# internal_excitation_w_gp.net
KiCad netlist of a schematic drawn in EAGLE
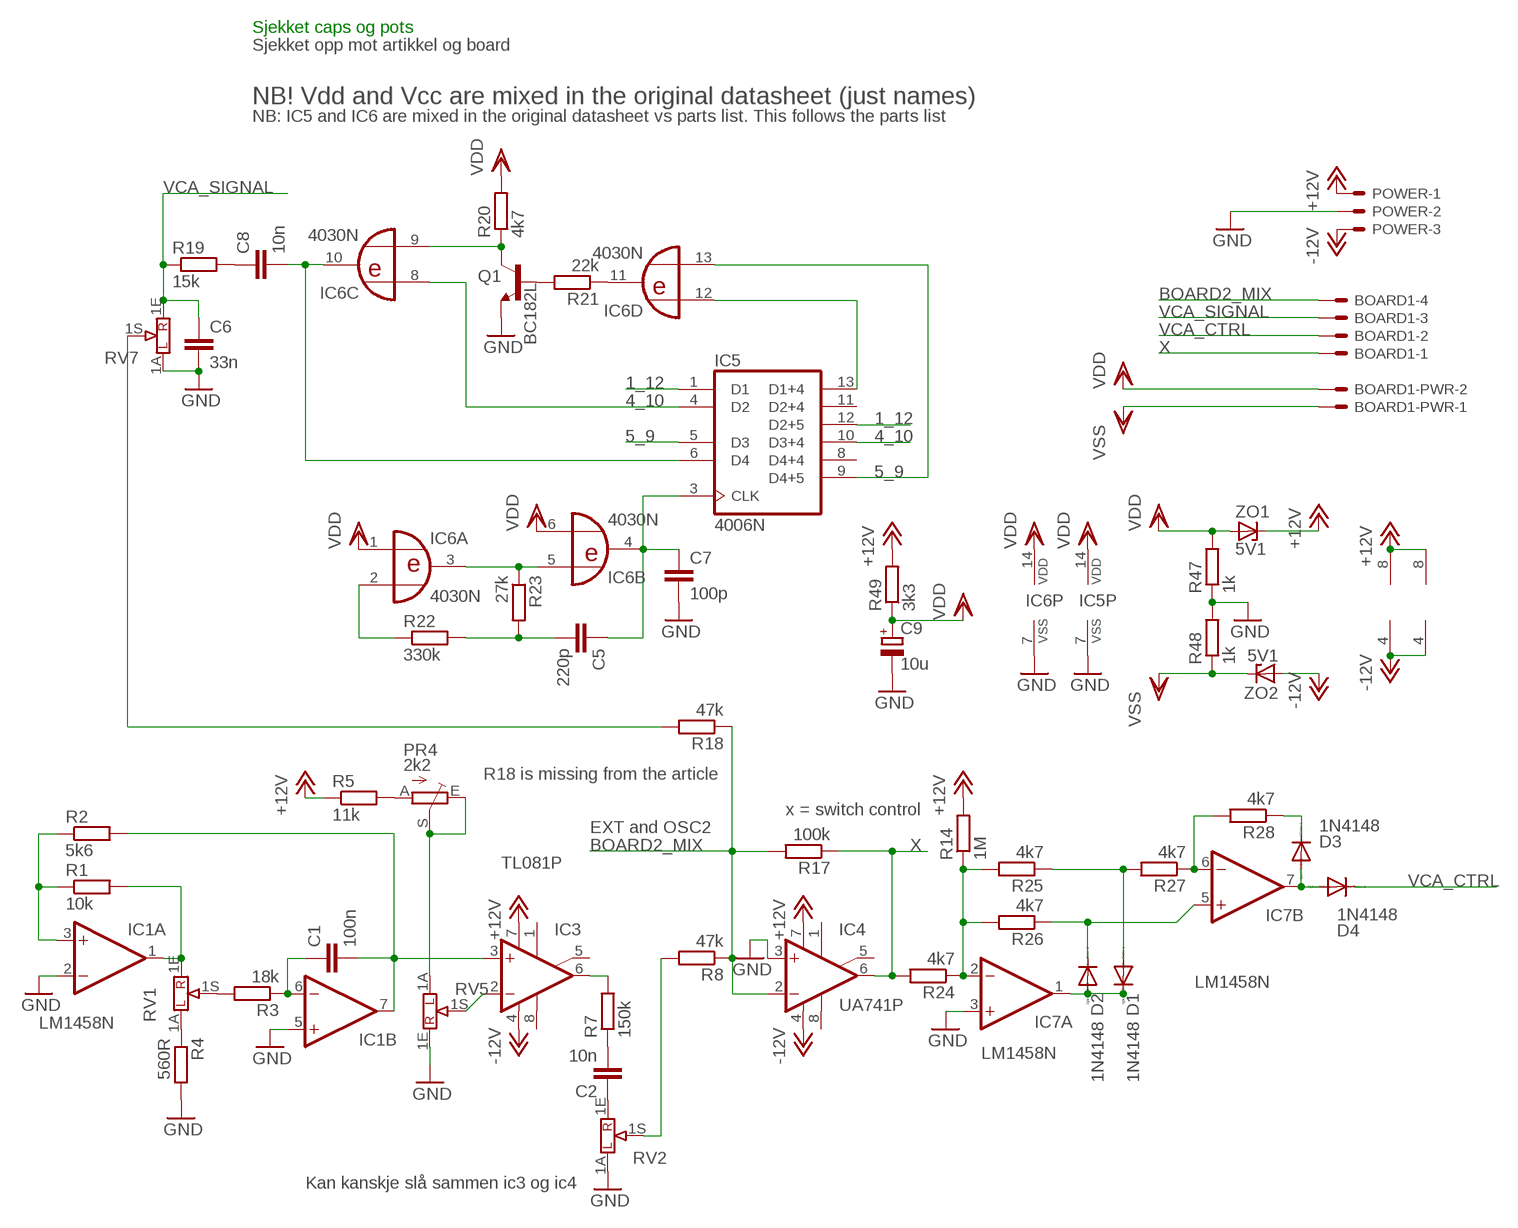
[diagram p0: schematic, sheet 1]

(export (version "E")
  (design (tool "Eeschema 10.0.6"))
  (components
    (comp (ref "BOARD1")
      (value "22-23-2041")
      (footprint "eagle-import:22-23-2041")
      (fields (field (name "MF") "MOLEX"))
      (libsource (lib "eagle-import") (part "22-23-2041"))
    )
    (comp (ref "BOARD1-PWR")
      (value "22-23-2021")
      (footprint "eagle-import:22-23-2021")
      (fields (field (name "MF") "MOLEX"))
      (libsource (lib "eagle-import") (part "22-23-2021"))
    )
    (comp (ref "C1")
      (value "100n")
      (footprint "eagle-import:C050-030X075")
      (libsource (lib "eagle-import") (part "C-EU050-030X075"))
    )
    (comp (ref "C2")
      (value "10n")
      (footprint "eagle-import:C025-025X050")
      (libsource (lib "eagle-import") (part "C-EU025-025X050"))
    )
    (comp (ref "C5")
      (value "220p")
      (footprint "eagle-import:C025-025X050")
      (libsource (lib "eagle-import") (part "C-EU025-025X050"))
    )
    (comp (ref "C6")
      (value "33n")
      (footprint "eagle-import:C050-030X075")
      (libsource (lib "eagle-import") (part "C-EU050-030X075"))
    )
    (comp (ref "C7")
      (value "100p")
      (footprint "eagle-import:C025-025X050")
      (libsource (lib "eagle-import") (part "C-EU025-025X050"))
    )
    (comp (ref "C8")
      (value "10n")
      (footprint "eagle-import:C050-030X075")
      (libsource (lib "eagle-import") (part "C-EU050-030X075"))
    )
    (comp (ref "C9")
      (value "10u")
      (footprint "eagle-import:E2,5-5")
      (libsource (lib "eagle-import") (part "CPOL-EUE2.5-5"))
    )
    (comp (ref "D1")
      (value "1N4148")
      (footprint "eagle-import:DO35-5J")
      (libsource (lib "eagle-import") (part "1N4148DOJ35-5"))
    )
    (comp (ref "D2")
      (value "1N4148")
      (footprint "eagle-import:DO35-5J")
      (libsource (lib "eagle-import") (part "1N4148DOJ35-5"))
    )
    (comp (ref "D3")
      (value "1N4148")
      (footprint "eagle-import:DO35-5J")
      (libsource (lib "eagle-import") (part "1N4148DOJ35-5"))
    )
    (comp (ref "D4")
      (value "1N4148")
      (footprint "eagle-import:DO35-5J")
      (libsource (lib "eagle-import") (part "1N4148DOJ35-5"))
    )
    (comp (ref "IC1")
      (value "LM1458N")
      (footprint "eagle-import:DIL08")
      (libsource (lib "eagle-import") (part "1458NLM"))
    )
    (comp (ref "IC3")
      (value "TL081P")
      (footprint "eagle-import:DIL08")
      (libsource (lib "eagle-import") (part "TL081P"))
    )
    (comp (ref "IC4")
      (value "UA741P")
      (footprint "eagle-import:DIL08")
      (libsource (lib "eagle-import") (part "741PUA"))
    )
    (comp (ref "IC5")
      (value "4006N")
      (footprint "eagle-import:DIL14")
      (libsource (lib "eagle-import") (part "4006N"))
    )
    (comp (ref "IC6")
      (value "4030N")
      (footprint "eagle-import:DIL14")
      (libsource (lib "eagle-import") (part "4030N"))
    )
    (comp (ref "IC7")
      (value "LM1458N")
      (footprint "eagle-import:DIL08")
      (libsource (lib "eagle-import") (part "1458NLM"))
    )
    (comp (ref "POWER")
      (value "KK-156-3")
      (footprint "eagle-import:KK-156-3")
      (libsource (lib "eagle-import") (part "KK-156-3"))
    )
    (comp (ref "PR4")
      (value "2k2")
      (footprint "eagle-import:CA9V")
      (libsource (lib "eagle-import") (part "TRIM_EU-CA9V"))
    )
    (comp (ref "Q1")
      (value "BC182L")
      (footprint "eagle-import:TO92-ECB")
      (libsource (lib "eagle-import") (part "-NPN-TO92-ECB"))
    )
    (comp (ref "R1")
      (value "10k")
      (footprint "eagle-import:0207_7")
      (libsource (lib "eagle-import") (part "R-EU_0207/7"))
    )
    (comp (ref "R2")
      (value "5k6")
      (footprint "eagle-import:0207_7")
      (libsource (lib "eagle-import") (part "R-EU_0207/7"))
    )
    (comp (ref "R3")
      (value "18k")
      (footprint "eagle-import:0207_7")
      (libsource (lib "eagle-import") (part "R-EU_0207/7"))
    )
    (comp (ref "R4")
      (value "560R")
      (footprint "eagle-import:0207_7")
      (libsource (lib "eagle-import") (part "R-EU_0207/7"))
    )
    (comp (ref "R5")
      (value "11k")
      (footprint "eagle-import:0207_7")
      (libsource (lib "eagle-import") (part "R-EU_0207/7"))
    )
    (comp (ref "R7")
      (value "150k")
      (footprint "eagle-import:0207_7")
      (libsource (lib "eagle-import") (part "R-EU_0207/7"))
    )
    (comp (ref "R8")
      (value "47k")
      (footprint "eagle-import:0207_7")
      (libsource (lib "eagle-import") (part "R-EU_0207/7"))
    )
    (comp (ref "R14")
      (value "1M")
      (footprint "eagle-import:0207_7")
      (libsource (lib "eagle-import") (part "R-EU_0207/7"))
    )
    (comp (ref "R17")
      (value "100k")
      (footprint "eagle-import:0207_7")
      (libsource (lib "eagle-import") (part "R-EU_0207/7"))
    )
    (comp (ref "R18")
      (value "47k")
      (footprint "eagle-import:0207_7")
      (libsource (lib "eagle-import") (part "R-EU_0207/7"))
    )
    (comp (ref "R19")
      (value "15k")
      (footprint "eagle-import:0207_7")
      (libsource (lib "eagle-import") (part "R-EU_0207/7"))
    )
    (comp (ref "R20")
      (value "4k7")
      (footprint "eagle-import:0207_7")
      (libsource (lib "eagle-import") (part "R-EU_0207/7"))
    )
    (comp (ref "R21")
      (value "22k")
      (footprint "eagle-import:0207_7")
      (libsource (lib "eagle-import") (part "R-EU_0207/7"))
    )
    (comp (ref "R22")
      (value "330k")
      (footprint "eagle-import:0207_7")
      (libsource (lib "eagle-import") (part "R-EU_0207/7"))
    )
    (comp (ref "R23")
      (value "27k")
      (footprint "eagle-import:0207_7")
      (libsource (lib "eagle-import") (part "R-EU_0207/7"))
    )
    (comp (ref "R24")
      (value "4k7")
      (footprint "eagle-import:0207_7")
      (libsource (lib "eagle-import") (part "R-EU_0207/7"))
    )
    (comp (ref "R25")
      (value "4k7")
      (footprint "eagle-import:0207_7")
      (libsource (lib "eagle-import") (part "R-EU_0207/7"))
    )
    (comp (ref "R26")
      (value "4k7")
      (footprint "eagle-import:0207_7")
      (libsource (lib "eagle-import") (part "R-EU_0207/7"))
    )
    (comp (ref "R27")
      (value "4k7")
      (footprint "eagle-import:0207_7")
      (libsource (lib "eagle-import") (part "R-EU_0207/7"))
    )
    (comp (ref "R28")
      (value "4k7")
      (footprint "eagle-import:0207_7")
      (libsource (lib "eagle-import") (part "R-EU_0207/7"))
    )
    (comp (ref "R47")
      (value "1k")
      (footprint "eagle-import:0207_7")
      (libsource (lib "eagle-import") (part "R-EU_0207/7"))
    )
    (comp (ref "R48")
      (value "1k")
      (footprint "eagle-import:0207_7")
      (libsource (lib "eagle-import") (part "R-EU_0207/7"))
    )
    (comp (ref "R49")
      (value "3k3")
      (footprint "eagle-import:0207_7")
      (libsource (lib "eagle-import") (part "R-EU_0207/7"))
    )
    (comp (ref "RV1")
      (value "10k log")
      (footprint "eagle-import:POT16_W_BRACKET")
      (libsource (lib "eagle-import") (part "POT16_W_BRACKET{dblquote}{dblquote}"))
    )
    (comp (ref "RV2")
      (value "10k log")
      (footprint "eagle-import:POT16_W_BRACKET")
      (libsource (lib "eagle-import") (part "POT16_W_BRACKET{dblquote}{dblquote}"))
    )
    (comp (ref "RV5")
      (value "10k")
      (footprint "eagle-import:POT16_W_BRACKET")
      (libsource (lib "eagle-import") (part "POT16_W_BRACKET{dblquote}{dblquote}"))
    )
    (comp (ref "RV7")
      (value "10k")
      (footprint "eagle-import:POT16_W_BRACKET")
      (libsource (lib "eagle-import") (part "POT16_W_BRACKET{dblquote}{dblquote}"))
    )
    (comp (ref "ZO1")
      (value "5V1")
      (footprint "eagle-import:ZDIO-5")
      (libsource (lib "eagle-import") (part "ZENER-DIODEZD-5"))
    )
    (comp (ref "ZO2")
      (value "5V1")
      (footprint "eagle-import:ZDIO-5")
      (libsource (lib "eagle-import") (part "ZENER-DIODEZD-5"))
    )
  )
  (nets
    (net (code "1") (name "+12V") (class "Default")
      (node (ref "IC1") (pin "8") (pinfunction "V+_8") (pintype "power_in"))
      (node (ref "IC3") (pin "7") (pinfunction "V+_7") (pintype "power_in"))
      (node (ref "IC4") (pin "7") (pinfunction "V+_7") (pintype "power_in"))
      (node (ref "IC7") (pin "8") (pinfunction "V+_8") (pintype "power_in"))
      (node (ref "POWER") (pin "1") (pinfunction "S_1") (pintype "passive"))
      (node (ref "R14") (pin "2") (pinfunction "2_2") (pintype "passive"))
      (node (ref "R49") (pin "2") (pinfunction "2_2") (pintype "passive"))
      (node (ref "R5") (pin "1") (pinfunction "1_1") (pintype "passive"))
      (node (ref "ZO1") (pin "C") (pinfunction "C_C") (pintype "passive"))
    )
    (net (code "2") (name "-12V") (class "Default")
      (node (ref "IC1") (pin "4") (pinfunction "V-_4") (pintype "power_in"))
      (node (ref "IC3") (pin "4") (pinfunction "V-_4") (pintype "power_in"))
      (node (ref "IC4") (pin "4") (pinfunction "V-_4") (pintype "power_in"))
      (node (ref "IC7") (pin "4") (pinfunction "V-_4") (pintype "power_in"))
      (node (ref "POWER") (pin "3") (pinfunction "S_3") (pintype "passive"))
      (node (ref "ZO2") (pin "A") (pinfunction "A_A") (pintype "passive"))
    )
    (net (code "3") (name "/1_12") (class "Default")
      (node (ref "IC5") (pin "1") (pinfunction "D1_1") (pintype "input"))
      (node (ref "IC5") (pin "12") (pinfunction "D2+5_12") (pintype "output"))
    )
    (net (code "4") (name "/4_10") (class "Default")
      (node (ref "IC5") (pin "10") (pinfunction "D3+4_10") (pintype "output"))
      (node (ref "IC5") (pin "4") (pinfunction "D2_4") (pintype "input"))
      (node (ref "IC6") (pin "8") (pinfunction "I0_8") (pintype "input"))
    )
    (net (code "5") (name "/5_9") (class "Default")
      (node (ref "IC5") (pin "5") (pinfunction "D3_5") (pintype "input"))
      (node (ref "IC5") (pin "9") (pinfunction "D4+5_9") (pintype "output"))
      (node (ref "IC6") (pin "13") (pinfunction "I1_13") (pintype "input"))
    )
    (net (code "6") (name "/BOARD2_MIX") (class "Default")
      (node (ref "BOARD1") (pin "4") (pinfunction "S_4") (pintype "passive"))
      (node (ref "IC4") (pin "2") (pinfunction "-IN_2") (pintype "input"))
      (node (ref "R17") (pin "2") (pinfunction "2_2") (pintype "passive"))
      (node (ref "R18") (pin "1") (pinfunction "1_1") (pintype "passive"))
      (node (ref "R8") (pin "1") (pinfunction "1_1") (pintype "passive"))
    )
    (net (code "7") (name "/VCA_CTRL") (class "Default")
      (node (ref "BOARD1") (pin "2") (pinfunction "S_2") (pintype "passive"))
      (node (ref "D4") (pin "C") (pinfunction "C_C") (pintype "passive"))
    )
    (net (code "8") (name "/VCA_SIGNAL") (class "Default")
      (node (ref "BOARD1") (pin "3") (pinfunction "S_3") (pintype "passive"))
      (node (ref "C6") (pin "1") (pinfunction "1_1") (pintype "passive"))
      (node (ref "R19") (pin "1") (pinfunction "1_1") (pintype "passive"))
      (node (ref "RV7") (pin "1E") (pinfunction "1E_1E") (pintype "passive"))
    )
    (net (code "9") (name "/X") (class "Default")
      (node (ref "BOARD1") (pin "1") (pinfunction "S_1") (pintype "passive"))
      (node (ref "IC4") (pin "6") (pinfunction "OUT_6") (pintype "output"))
      (node (ref "R17") (pin "1") (pinfunction "1_1") (pintype "passive"))
      (node (ref "R24") (pin "2") (pinfunction "2_2") (pintype "passive"))
    )
    (net (code "10") (name "GND") (class "Default")
      (node (ref "C6") (pin "2") (pinfunction "2_2") (pintype "passive"))
      (node (ref "C7") (pin "2") (pinfunction "2_2") (pintype "passive"))
      (node (ref "C9") (pin "-") (pinfunction "-_-") (pintype "passive"))
      (node (ref "IC1") (pin "2") (pinfunction "-IN_2") (pintype "input"))
      (node (ref "IC1") (pin "5") (pinfunction "+IN_5") (pintype "input"))
      (node (ref "IC4") (pin "3") (pinfunction "+IN_3") (pintype "input"))
      (node (ref "IC5") (pin "7") (pinfunction "VSS_7") (pintype "power_in"))
      (node (ref "IC6") (pin "7") (pinfunction "VSS_7") (pintype "power_in"))
      (node (ref "IC7") (pin "3") (pinfunction "+IN_3") (pintype "input"))
      (node (ref "POWER") (pin "2") (pinfunction "S_2") (pintype "passive"))
      (node (ref "Q1") (pin "E") (pinfunction "E_E") (pintype "passive"))
      (node (ref "R4") (pin "2") (pinfunction "2_2") (pintype "passive"))
      (node (ref "R47") (pin "1") (pinfunction "1_1") (pintype "passive"))
      (node (ref "R48") (pin "2") (pinfunction "2_2") (pintype "passive"))
      (node (ref "RV2") (pin "1A") (pinfunction "1A_1A") (pintype "passive"))
      (node (ref "RV5") (pin "1E") (pinfunction "1E_1E") (pintype "passive"))
      (node (ref "RV7") (pin "1A") (pinfunction "1A_1A") (pintype "passive"))
    )
    (net (code "11") (name "Net-(C2-Pad1)") (class "Default")
      (node (ref "C2") (pin "1") (pinfunction "1_1") (pintype "passive"))
      (node (ref "RV2") (pin "1E") (pinfunction "1E_1E") (pintype "passive"))
    )
    (net (code "12") (name "Net-(C2-Pad2)") (class "Default")
      (node (ref "C2") (pin "2") (pinfunction "2_2") (pintype "passive"))
      (node (ref "R7") (pin "1") (pinfunction "1_1") (pintype "passive"))
    )
    (net (code "13") (name "Net-(C5-Pad2)") (class "Default")
      (node (ref "C5") (pin "2") (pinfunction "2_2") (pintype "passive"))
      (node (ref "R22") (pin "2") (pinfunction "2_2") (pintype "passive"))
      (node (ref "R23") (pin "2") (pinfunction "2_2") (pintype "passive"))
    )
    (net (code "14") (name "Net-(C8-Pad1)") (class "Default")
      (node (ref "C8") (pin "1") (pinfunction "1_1") (pintype "passive"))
      (node (ref "R19") (pin "2") (pinfunction "2_2") (pintype "passive"))
    )
    (net (code "15") (name "Net-(D1-PadA)") (class "Default")
      (node (ref "D1") (pin "A") (pinfunction "A_A") (pintype "passive"))
      (node (ref "R25") (pin "1") (pinfunction "1_1") (pintype "passive"))
      (node (ref "R27") (pin "2") (pinfunction "2_2") (pintype "passive"))
    )
    (net (code "16") (name "Net-(D3-PadC)") (class "Default")
      (node (ref "D3") (pin "C") (pinfunction "C_C") (pintype "passive"))
      (node (ref "R28") (pin "1") (pinfunction "1_1") (pintype "passive"))
    )
    (net (code "17") (name "Net-(IC1A-+IN)") (class "Default")
      (node (ref "IC1") (pin "3") (pinfunction "+IN_3") (pintype "input"))
      (node (ref "R1") (pin "1") (pinfunction "1_1") (pintype "passive"))
      (node (ref "R2") (pin "1") (pinfunction "1_1") (pintype "passive"))
    )
    (net (code "18") (name "Net-(IC1A-OUT)") (class "Default")
      (node (ref "IC1") (pin "1") (pinfunction "OUT_1") (pintype "output"))
      (node (ref "R1") (pin "2") (pinfunction "2_2") (pintype "passive"))
      (node (ref "RV1") (pin "1E") (pinfunction "1E_1E") (pintype "passive"))
    )
    (net (code "19") (name "Net-(IC1B--IN)") (class "Default")
      (node (ref "C1") (pin "1") (pinfunction "1_1") (pintype "passive"))
      (node (ref "IC1") (pin "6") (pinfunction "-IN_6") (pintype "input"))
      (node (ref "R3") (pin "1") (pinfunction "1_1") (pintype "passive"))
    )
    (net (code "20") (name "Net-(IC1B-OUT)") (class "Default")
      (node (ref "C1") (pin "2") (pinfunction "2_2") (pintype "passive"))
      (node (ref "IC1") (pin "7") (pinfunction "OUT_7") (pintype "output"))
      (node (ref "IC3") (pin "3") (pinfunction "+IN_3") (pintype "input"))
      (node (ref "R2") (pin "2") (pinfunction "2_2") (pintype "passive"))
    )
    (net (code "21") (name "Net-(IC3--IN)") (class "Default")
      (node (ref "IC3") (pin "2") (pinfunction "-IN_2") (pintype "input"))
      (node (ref "RV5") (pin "1S") (pinfunction "1S_1S") (pintype "passive"))
    )
    (net (code "22") (name "Net-(IC3-OUT)") (class "Default")
      (node (ref "IC3") (pin "6") (pinfunction "OUT_6") (pintype "output"))
      (node (ref "R7") (pin "2") (pinfunction "2_2") (pintype "passive"))
    )
    (net (code "23") (name "Net-(IC5A-CLK)") (class "Default")
      (node (ref "C5") (pin "1") (pinfunction "1_1") (pintype "passive"))
      (node (ref "C7") (pin "1") (pinfunction "1_1") (pintype "passive"))
      (node (ref "IC5") (pin "3") (pinfunction "CLK_3") (pintype "input"))
      (node (ref "IC6") (pin "4") (pinfunction "O_4") (pintype "output"))
    )
    (net (code "24") (name "Net-(IC5A-D1+4)") (class "Default")
      (node (ref "IC5") (pin "13") (pinfunction "D1+4_13") (pintype "output"))
      (node (ref "IC6") (pin "12") (pinfunction "I0_12") (pintype "input"))
    )
    (net (code "25") (name "Net-(IC5A-D4)") (class "Default")
      (node (ref "C8") (pin "2") (pinfunction "2_2") (pintype "passive"))
      (node (ref "IC5") (pin "6") (pinfunction "D4_6") (pintype "input"))
      (node (ref "IC6") (pin "10") (pinfunction "O_10") (pintype "output"))
    )
    (net (code "26") (name "Net-(IC6A-I1)") (class "Default")
      (node (ref "IC6") (pin "2") (pinfunction "I1_2") (pintype "input"))
      (node (ref "R22") (pin "1") (pinfunction "1_1") (pintype "passive"))
    )
    (net (code "27") (name "Net-(IC6A-O)") (class "Default")
      (node (ref "IC6") (pin "3") (pinfunction "O_3") (pintype "output"))
      (node (ref "IC6") (pin "5") (pinfunction "I0_5") (pintype "input"))
      (node (ref "R23") (pin "1") (pinfunction "1_1") (pintype "passive"))
    )
    (net (code "28") (name "Net-(IC6C-I1)") (class "Default")
      (node (ref "IC6") (pin "9") (pinfunction "I1_9") (pintype "input"))
      (node (ref "Q1") (pin "C") (pinfunction "C_C") (pintype "passive"))
      (node (ref "R20") (pin "1") (pinfunction "1_1") (pintype "passive"))
    )
    (net (code "29") (name "Net-(IC6D-O)") (class "Default")
      (node (ref "IC6") (pin "11") (pinfunction "O_11") (pintype "output"))
      (node (ref "R21") (pin "1") (pinfunction "1_1") (pintype "passive"))
    )
    (net (code "30") (name "Net-(IC7A--IN)") (class "Default")
      (node (ref "IC7") (pin "2") (pinfunction "-IN_2") (pintype "input"))
      (node (ref "R14") (pin "1") (pinfunction "1_1") (pintype "passive"))
      (node (ref "R24") (pin "1") (pinfunction "1_1") (pintype "passive"))
      (node (ref "R25") (pin "2") (pinfunction "2_2") (pintype "passive"))
      (node (ref "R26") (pin "2") (pinfunction "2_2") (pintype "passive"))
    )
    (net (code "31") (name "Net-(IC7A-OUT)") (class "Default")
      (node (ref "D1") (pin "C") (pinfunction "C_C") (pintype "passive"))
      (node (ref "D2") (pin "A") (pinfunction "A_A") (pintype "passive"))
      (node (ref "IC7") (pin "1") (pinfunction "OUT_1") (pintype "output"))
    )
    (net (code "32") (name "Net-(IC7B-+IN)") (class "Default")
      (node (ref "D2") (pin "C") (pinfunction "C_C") (pintype "passive"))
      (node (ref "IC7") (pin "5") (pinfunction "+IN_5") (pintype "input"))
      (node (ref "R26") (pin "1") (pinfunction "1_1") (pintype "passive"))
    )
    (net (code "33") (name "Net-(IC7B--IN)") (class "Default")
      (node (ref "IC7") (pin "6") (pinfunction "-IN_6") (pintype "input"))
      (node (ref "R27") (pin "1") (pinfunction "1_1") (pintype "passive"))
      (node (ref "R28") (pin "2") (pinfunction "2_2") (pintype "passive"))
    )
    (net (code "34") (name "Net-(IC7B-OUT)") (class "Default")
      (node (ref "D3") (pin "A") (pinfunction "A_A") (pintype "passive"))
      (node (ref "D4") (pin "A") (pinfunction "A_A") (pintype "passive"))
      (node (ref "IC7") (pin "7") (pinfunction "OUT_7") (pintype "output"))
    )
    (net (code "35") (name "Net-(PR4-PadA)") (class "Default")
      (node (ref "PR4") (pin "A") (pinfunction "A_A") (pintype "passive"))
      (node (ref "R5") (pin "2") (pinfunction "2_2") (pintype "passive"))
    )
    (net (code "36") (name "Net-(PR4-PadE)") (class "Default")
      (node (ref "PR4") (pin "E") (pinfunction "E_E") (pintype "passive"))
      (node (ref "PR4") (pin "S") (pinfunction "S_S") (pintype "passive"))
      (node (ref "RV5") (pin "1A") (pinfunction "1A_1A") (pintype "passive"))
    )
    (net (code "37") (name "Net-(Q1-PadB)") (class "Default")
      (node (ref "Q1") (pin "B") (pinfunction "B_B") (pintype "passive"))
      (node (ref "R21") (pin "2") (pinfunction "2_2") (pintype "passive"))
    )
    (net (code "38") (name "Net-(R3-Pad2)") (class "Default")
      (node (ref "R3") (pin "2") (pinfunction "2_2") (pintype "passive"))
      (node (ref "RV1") (pin "1S") (pinfunction "1S_1S") (pintype "passive"))
    )
    (net (code "39") (name "Net-(R4-Pad1)") (class "Default")
      (node (ref "R4") (pin "1") (pinfunction "1_1") (pintype "passive"))
      (node (ref "RV1") (pin "1A") (pinfunction "1A_1A") (pintype "passive"))
    )
    (net (code "40") (name "Net-(R8-Pad2)") (class "Default")
      (node (ref "R8") (pin "2") (pinfunction "2_2") (pintype "passive"))
      (node (ref "RV2") (pin "1S") (pinfunction "1S_1S") (pintype "passive"))
    )
    (net (code "41") (name "Net-(R18-Pad2)") (class "Default")
      (node (ref "R18") (pin "2") (pinfunction "2_2") (pintype "passive"))
      (node (ref "RV7") (pin "1S") (pinfunction "1S_1S") (pintype "passive"))
    )
    (net (code "42") (name "VDD") (class "Default")
      (node (ref "BOARD1-PWR") (pin "2") (pinfunction "S_2") (pintype "passive"))
      (node (ref "C9") (pin "+") (pinfunction "+_+") (pintype "passive"))
      (node (ref "IC5") (pin "14") (pinfunction "VDD_14") (pintype "power_in"))
      (node (ref "IC6") (pin "1") (pinfunction "I0_1") (pintype "input"))
      (node (ref "IC6") (pin "14") (pinfunction "VDD_14") (pintype "power_in"))
      (node (ref "IC6") (pin "6") (pinfunction "I1_6") (pintype "input"))
      (node (ref "R20") (pin "2") (pinfunction "2_2") (pintype "passive"))
      (node (ref "R47") (pin "2") (pinfunction "2_2") (pintype "passive"))
      (node (ref "R49") (pin "1") (pinfunction "1_1") (pintype "passive"))
      (node (ref "ZO1") (pin "A") (pinfunction "A_A") (pintype "passive"))
    )
    (net (code "43") (name "VSS") (class "Default")
      (node (ref "BOARD1-PWR") (pin "1") (pinfunction "S_1") (pintype "passive"))
      (node (ref "R48") (pin "1") (pinfunction "1_1") (pintype "passive"))
      (node (ref "ZO2") (pin "C") (pinfunction "C_C") (pintype "passive"))
    )
    (net (code "44") (name "unconnected-(IC3-ON1-Pad1)") (class "Default")
      (node (ref "IC3") (pin "1") (pinfunction "ON1_1") (pintype "passive"))
    )
    (net (code "45") (name "unconnected-(IC3-ON2-Pad5)") (class "Default")
      (node (ref "IC3") (pin "5") (pinfunction "ON2_5") (pintype "passive"))
    )
    (net (code "46") (name "unconnected-(IC3-OPT-Pad8)") (class "Default")
      (node (ref "IC3") (pin "8") (pinfunction "OPT_8") (pintype "passive"))
    )
    (net (code "47") (name "unconnected-(IC4-ON1-Pad1)") (class "Default")
      (node (ref "IC4") (pin "1") (pinfunction "ON1_1") (pintype "passive"))
    )
    (net (code "48") (name "unconnected-(IC4-ON2-Pad5)") (class "Default")
      (node (ref "IC4") (pin "5") (pinfunction "ON2_5") (pintype "passive"))
    )
    (net (code "49") (name "unconnected-(IC4-OPT-Pad8)") (class "Default")
      (node (ref "IC4") (pin "8") (pinfunction "OPT_8") (pintype "passive"))
    )
    (net (code "50") (name "unconnected-(IC5A-D2+4-Pad11)") (class "Default")
      (node (ref "IC5") (pin "11") (pinfunction "D2+4_11") (pintype "output"))
    )
    (net (code "51") (name "unconnected-(IC5A-D4+4-Pad8)") (class "Default")
      (node (ref "IC5") (pin "8") (pinfunction "D4+4_8") (pintype "output"))
    )
  )
)
